# PHP.net
KiCad netlist of a schematic drawn in Altium Designer
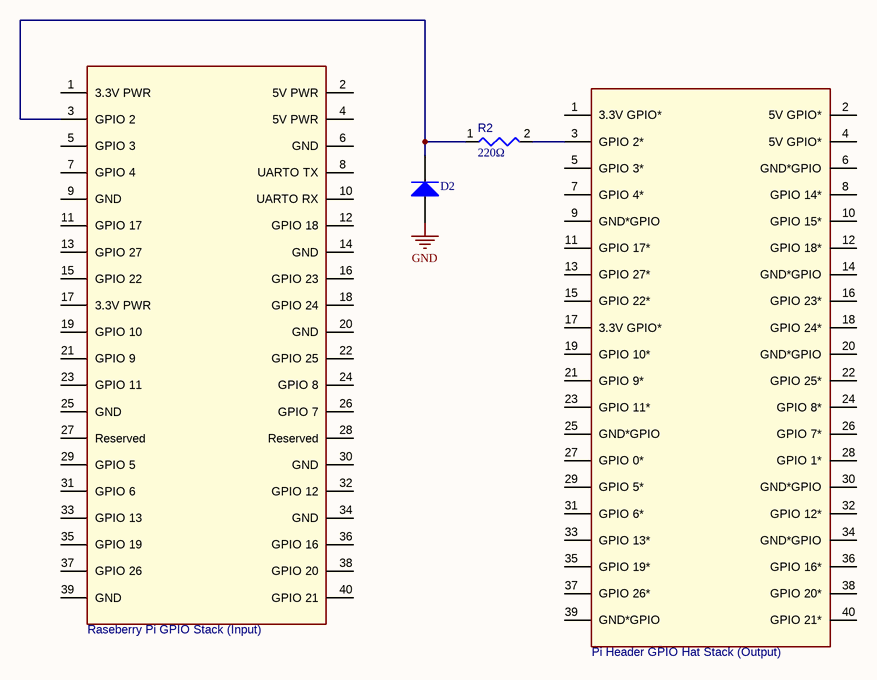
[diagram p0: PHP.SchDoc]

(export (version "E")
  (design (tool "Eeschema 10.0.6"))
  (components
    (comp (ref "D2")
      (value "1N4148")
      (footprint "NXP-SOD27-2_V")
      (description "High Speed Diode, 100 V, 0.45 A, -65 to 175 degC, 2-Pin SOD27, RoHS, Bulk")
      (fields (field (name "POWER") "500mW") (field (name "MANUFACTURER") "Fairchild"))
      (libsource (lib "Alexander Egan") (part "D-AK-2"))
    )
    (comp (ref "J1")
      (value "Raseberry Pi GPIO Stack (Input)")
      (footprint "TECO-1746540-4_V")
      (description "Connector")
      (libsource (lib "") (part "CMP-02187-7_1"))
    )
    (comp (ref "J2")
      (value "Pi Header GPIO Hat Stack (Output)")
      (footprint "TECO-1746540-4_V")
      (description "Connector")
      (libsource (lib "CMP-02187-7") (part "CMP-02187-7"))
    )
    (comp (ref "R2")
      (value "220Ω")
      (footprint "RESC1608X55X25ML10T15")
      (description "Chip Resistor, 4.7 KOhm, +/- 1%, 0.1 W, -55 to 155 degC, 0603 (1608 Metric)")
      (fields (field (name "TOLERANCE") "1%") (field (name "POWER") "100mW"))
      (libsource (lib "Alexander Egan") (part "RES-2"))
    )
  )
  (nets
    (net (code "1") (name "GND") (class "Default")
      (node (ref "D2") (pin "1") (pinfunction "A_1") (pintype "passive"))
    )
    (net (code "2") (name "Net-(D2-K)") (class "Default")
      (node (ref "D2") (pin "2") (pinfunction "K_2") (pintype "passive"))
      (node (ref "J1") (pin "3") (pinfunction "GPIO_2_3") (pintype "passive"))
      (node (ref "R2") (pin "1") (pinfunction "1_1") (pintype "passive"))
    )
    (net (code "3") (name "Net-(J2B-GPIO_2*)") (class "Default")
      (node (ref "J2") (pin "3") (pinfunction "GPIO_2*_3") (pintype "passive"))
      (node (ref "R2") (pin "2") (pinfunction "2_2") (pintype "passive"))
    )
    (net (code "4") (name "unconnected-(J1-3.3V_PWR-Pad1)") (class "Default")
      (node (ref "J1") (pin "1") (pinfunction "3.3V_PWR_1") (pintype "passive"))
    )
    (net (code "5") (name "unconnected-(J1-3.3V_PWR-Pad17)") (class "Default")
      (node (ref "J1") (pin "17") (pinfunction "3.3V_PWR_17") (pintype "passive"))
    )
    (net (code "6") (name "unconnected-(J1-5V_PWR-Pad2)") (class "Default")
      (node (ref "J1") (pin "2") (pinfunction "5V_PWR_2") (pintype "passive"))
    )
    (net (code "7") (name "unconnected-(J1-5V_PWR-Pad4)") (class "Default")
      (node (ref "J1") (pin "4") (pinfunction "5V_PWR_4") (pintype "passive"))
    )
    (net (code "8") (name "unconnected-(J1-GND-Pad6)") (class "Default")
      (node (ref "J1") (pin "6") (pinfunction "GND_6") (pintype "passive"))
    )
    (net (code "9") (name "unconnected-(J1-GND-Pad9)") (class "Default")
      (node (ref "J1") (pin "9") (pinfunction "GND_9") (pintype "passive"))
    )
    (net (code "10") (name "unconnected-(J1-GND-Pad14)") (class "Default")
      (node (ref "J1") (pin "14") (pinfunction "GND_14") (pintype "passive"))
    )
    (net (code "11") (name "unconnected-(J1-GND-Pad20)") (class "Default")
      (node (ref "J1") (pin "20") (pinfunction "GND_20") (pintype "passive"))
    )
    (net (code "12") (name "unconnected-(J1-GND-Pad25)") (class "Default")
      (node (ref "J1") (pin "25") (pinfunction "GND_25") (pintype "passive"))
    )
    (net (code "13") (name "unconnected-(J1-GND-Pad30)") (class "Default")
      (node (ref "J1") (pin "30") (pinfunction "GND_30") (pintype "passive"))
    )
    (net (code "14") (name "unconnected-(J1-GND-Pad34)") (class "Default")
      (node (ref "J1") (pin "34") (pinfunction "GND_34") (pintype "passive"))
    )
    (net (code "15") (name "unconnected-(J1-GND-Pad39)") (class "Default")
      (node (ref "J1") (pin "39") (pinfunction "GND_39") (pintype "passive"))
    )
    (net (code "16") (name "unconnected-(J1-GPIO_3-Pad5)") (class "Default")
      (node (ref "J1") (pin "5") (pinfunction "GPIO_3_5") (pintype "passive"))
    )
    (net (code "17") (name "unconnected-(J1-GPIO_4-Pad7)") (class "Default")
      (node (ref "J1") (pin "7") (pinfunction "GPIO_4_7") (pintype "passive"))
    )
    (net (code "18") (name "unconnected-(J1-GPIO_5-Pad29)") (class "Default")
      (node (ref "J1") (pin "29") (pinfunction "GPIO_5_29") (pintype "passive"))
    )
    (net (code "19") (name "unconnected-(J1-GPIO_6-Pad31)") (class "Default")
      (node (ref "J1") (pin "31") (pinfunction "GPIO_6_31") (pintype "passive"))
    )
    (net (code "20") (name "unconnected-(J1-GPIO_7-Pad26)") (class "Default")
      (node (ref "J1") (pin "26") (pinfunction "GPIO_7_26") (pintype "passive"))
    )
    (net (code "21") (name "unconnected-(J1-GPIO_8-Pad24)") (class "Default")
      (node (ref "J1") (pin "24") (pinfunction "GPIO_8_24") (pintype "passive"))
    )
    (net (code "22") (name "unconnected-(J1-GPIO_9-Pad21)") (class "Default")
      (node (ref "J1") (pin "21") (pinfunction "GPIO_9_21") (pintype "passive"))
    )
    (net (code "23") (name "unconnected-(J1-GPIO_10-Pad19)") (class "Default")
      (node (ref "J1") (pin "19") (pinfunction "GPIO_10_19") (pintype "passive"))
    )
    (net (code "24") (name "unconnected-(J1-GPIO_11-Pad23)") (class "Default")
      (node (ref "J1") (pin "23") (pinfunction "GPIO_11_23") (pintype "passive"))
    )
    (net (code "25") (name "unconnected-(J1-GPIO_12-Pad32)") (class "Default")
      (node (ref "J1") (pin "32") (pinfunction "GPIO_12_32") (pintype "passive"))
    )
    (net (code "26") (name "unconnected-(J1-GPIO_13-Pad33)") (class "Default")
      (node (ref "J1") (pin "33") (pinfunction "GPIO_13_33") (pintype "passive"))
    )
    (net (code "27") (name "unconnected-(J1-GPIO_16-Pad36)") (class "Default")
      (node (ref "J1") (pin "36") (pinfunction "GPIO_16_36") (pintype "passive"))
    )
    (net (code "28") (name "unconnected-(J1-GPIO_17-Pad11)") (class "Default")
      (node (ref "J1") (pin "11") (pinfunction "GPIO_17_11") (pintype "passive"))
    )
    (net (code "29") (name "unconnected-(J1-GPIO_18-Pad12)") (class "Default")
      (node (ref "J1") (pin "12") (pinfunction "GPIO_18_12") (pintype "passive"))
    )
    (net (code "30") (name "unconnected-(J1-GPIO_19-Pad35)") (class "Default")
      (node (ref "J1") (pin "35") (pinfunction "GPIO_19_35") (pintype "passive"))
    )
    (net (code "31") (name "unconnected-(J1-GPIO_20-Pad38)") (class "Default")
      (node (ref "J1") (pin "38") (pinfunction "GPIO_20_38") (pintype "passive"))
    )
    (net (code "32") (name "unconnected-(J1-GPIO_21-Pad40)") (class "Default")
      (node (ref "J1") (pin "40") (pinfunction "GPIO_21_40") (pintype "passive"))
    )
    (net (code "33") (name "unconnected-(J1-GPIO_22-Pad15)") (class "Default")
      (node (ref "J1") (pin "15") (pinfunction "GPIO_22_15") (pintype "passive"))
    )
    (net (code "34") (name "unconnected-(J1-GPIO_23-Pad16)") (class "Default")
      (node (ref "J1") (pin "16") (pinfunction "GPIO_23_16") (pintype "passive"))
    )
    (net (code "35") (name "unconnected-(J1-GPIO_24-Pad18)") (class "Default")
      (node (ref "J1") (pin "18") (pinfunction "GPIO_24_18") (pintype "passive"))
    )
    (net (code "36") (name "unconnected-(J1-GPIO_25-Pad22)") (class "Default")
      (node (ref "J1") (pin "22") (pinfunction "GPIO_25_22") (pintype "passive"))
    )
    (net (code "37") (name "unconnected-(J1-GPIO_26-Pad37)") (class "Default")
      (node (ref "J1") (pin "37") (pinfunction "GPIO_26_37") (pintype "passive"))
    )
    (net (code "38") (name "unconnected-(J1-GPIO_27-Pad13)") (class "Default")
      (node (ref "J1") (pin "13") (pinfunction "GPIO_27_13") (pintype "passive"))
    )
    (net (code "39") (name "unconnected-(J1-Reserved-Pad27)") (class "Default")
      (node (ref "J1") (pin "27") (pinfunction "Reserved_27") (pintype "passive"))
    )
    (net (code "40") (name "unconnected-(J1-Reserved-Pad28)") (class "Default")
      (node (ref "J1") (pin "28") (pinfunction "Reserved_28") (pintype "passive"))
    )
    (net (code "41") (name "unconnected-(J1-UARTO_RX-Pad10)") (class "Default")
      (node (ref "J1") (pin "10") (pinfunction "UARTO_RX_10") (pintype "passive"))
    )
    (net (code "42") (name "unconnected-(J1-UARTO_TX-Pad8)") (class "Default")
      (node (ref "J1") (pin "8") (pinfunction "UARTO_TX_8") (pintype "passive"))
    )
    (net (code "43") (name "unconnected-(J2B-3.3V_GPIO*-Pad1)") (class "Default")
      (node (ref "J2") (pin "1") (pinfunction "3.3V_GPIO*_1") (pintype "passive"))
    )
    (net (code "44") (name "unconnected-(J2B-3.3V_GPIO*-Pad17)") (class "Default")
      (node (ref "J2") (pin "17") (pinfunction "3.3V_GPIO*_17") (pintype "passive"))
    )
    (net (code "45") (name "unconnected-(J2B-5V_GPIO*-Pad2)") (class "Default")
      (node (ref "J2") (pin "2") (pinfunction "5V_GPIO*_2") (pintype "passive"))
    )
    (net (code "46") (name "unconnected-(J2B-5V_GPIO*-Pad4)") (class "Default")
      (node (ref "J2") (pin "4") (pinfunction "5V_GPIO*_4") (pintype "passive"))
    )
    (net (code "47") (name "unconnected-(J2B-GND*GPIO-Pad6)") (class "Default")
      (node (ref "J2") (pin "6") (pinfunction "GND*GPIO_6") (pintype "passive"))
    )
    (net (code "48") (name "unconnected-(J2B-GND*GPIO-Pad9)") (class "Default")
      (node (ref "J2") (pin "9") (pinfunction "GND*GPIO_9") (pintype "passive"))
    )
    (net (code "49") (name "unconnected-(J2B-GND*GPIO-Pad14)") (class "Default")
      (node (ref "J2") (pin "14") (pinfunction "GND*GPIO_14") (pintype "passive"))
    )
    (net (code "50") (name "unconnected-(J2B-GND*GPIO-Pad20)") (class "Default")
      (node (ref "J2") (pin "20") (pinfunction "GND*GPIO_20") (pintype "passive"))
    )
    (net (code "51") (name "unconnected-(J2B-GND*GPIO-Pad25)") (class "Default")
      (node (ref "J2") (pin "25") (pinfunction "GND*GPIO_25") (pintype "passive"))
    )
    (net (code "52") (name "unconnected-(J2B-GND*GPIO-Pad30)") (class "Default")
      (node (ref "J2") (pin "30") (pinfunction "GND*GPIO_30") (pintype "passive"))
    )
    (net (code "53") (name "unconnected-(J2B-GND*GPIO-Pad34)") (class "Default")
      (node (ref "J2") (pin "34") (pinfunction "GND*GPIO_34") (pintype "passive"))
    )
    (net (code "54") (name "unconnected-(J2B-GND*GPIO-Pad39)") (class "Default")
      (node (ref "J2") (pin "39") (pinfunction "GND*GPIO_39") (pintype "passive"))
    )
    (net (code "55") (name "unconnected-(J2B-GPIO_0*-Pad27)") (class "Default")
      (node (ref "J2") (pin "27") (pinfunction "GPIO_0*_27") (pintype "passive"))
    )
    (net (code "56") (name "unconnected-(J2B-GPIO_1*-Pad28)") (class "Default")
      (node (ref "J2") (pin "28") (pinfunction "GPIO_1*_28") (pintype "passive"))
    )
    (net (code "57") (name "unconnected-(J2B-GPIO_3*-Pad5)") (class "Default")
      (node (ref "J2") (pin "5") (pinfunction "GPIO_3*_5") (pintype "passive"))
    )
    (net (code "58") (name "unconnected-(J2B-GPIO_4*-Pad7)") (class "Default")
      (node (ref "J2") (pin "7") (pinfunction "GPIO_4*_7") (pintype "passive"))
    )
    (net (code "59") (name "unconnected-(J2B-GPIO_5*-Pad29)") (class "Default")
      (node (ref "J2") (pin "29") (pinfunction "GPIO_5*_29") (pintype "passive"))
    )
    (net (code "60") (name "unconnected-(J2B-GPIO_6*-Pad31)") (class "Default")
      (node (ref "J2") (pin "31") (pinfunction "GPIO_6*_31") (pintype "passive"))
    )
    (net (code "61") (name "unconnected-(J2B-GPIO_7*-Pad26)") (class "Default")
      (node (ref "J2") (pin "26") (pinfunction "GPIO_7*_26") (pintype "passive"))
    )
    (net (code "62") (name "unconnected-(J2B-GPIO_8*-Pad24)") (class "Default")
      (node (ref "J2") (pin "24") (pinfunction "GPIO_8*_24") (pintype "passive"))
    )
    (net (code "63") (name "unconnected-(J2B-GPIO_9*-Pad21)") (class "Default")
      (node (ref "J2") (pin "21") (pinfunction "GPIO_9*_21") (pintype "passive"))
    )
    (net (code "64") (name "unconnected-(J2B-GPIO_10*-Pad19)") (class "Default")
      (node (ref "J2") (pin "19") (pinfunction "GPIO_10*_19") (pintype "passive"))
    )
    (net (code "65") (name "unconnected-(J2B-GPIO_11*-Pad23)") (class "Default")
      (node (ref "J2") (pin "23") (pinfunction "GPIO_11*_23") (pintype "passive"))
    )
    (net (code "66") (name "unconnected-(J2B-GPIO_12*-Pad32)") (class "Default")
      (node (ref "J2") (pin "32") (pinfunction "GPIO_12*_32") (pintype "passive"))
    )
    (net (code "67") (name "unconnected-(J2B-GPIO_13*-Pad33)") (class "Default")
      (node (ref "J2") (pin "33") (pinfunction "GPIO_13*_33") (pintype "passive"))
    )
    (net (code "68") (name "unconnected-(J2B-GPIO_14*-Pad8)") (class "Default")
      (node (ref "J2") (pin "8") (pinfunction "GPIO_14*_8") (pintype "passive"))
    )
    (net (code "69") (name "unconnected-(J2B-GPIO_15*-Pad10)") (class "Default")
      (node (ref "J2") (pin "10") (pinfunction "GPIO_15*_10") (pintype "passive"))
    )
    (net (code "70") (name "unconnected-(J2B-GPIO_16*-Pad36)") (class "Default")
      (node (ref "J2") (pin "36") (pinfunction "GPIO_16*_36") (pintype "passive"))
    )
    (net (code "71") (name "unconnected-(J2B-GPIO_17*-Pad11)") (class "Default")
      (node (ref "J2") (pin "11") (pinfunction "GPIO_17*_11") (pintype "passive"))
    )
    (net (code "72") (name "unconnected-(J2B-GPIO_18*-Pad12)") (class "Default")
      (node (ref "J2") (pin "12") (pinfunction "GPIO_18*_12") (pintype "passive"))
    )
    (net (code "73") (name "unconnected-(J2B-GPIO_19*-Pad35)") (class "Default")
      (node (ref "J2") (pin "35") (pinfunction "GPIO_19*_35") (pintype "passive"))
    )
    (net (code "74") (name "unconnected-(J2B-GPIO_20*-Pad38)") (class "Default")
      (node (ref "J2") (pin "38") (pinfunction "GPIO_20*_38") (pintype "passive"))
    )
    (net (code "75") (name "unconnected-(J2B-GPIO_21*-Pad40)") (class "Default")
      (node (ref "J2") (pin "40") (pinfunction "GPIO_21*_40") (pintype "passive"))
    )
    (net (code "76") (name "unconnected-(J2B-GPIO_22*-Pad15)") (class "Default")
      (node (ref "J2") (pin "15") (pinfunction "GPIO_22*_15") (pintype "passive"))
    )
    (net (code "77") (name "unconnected-(J2B-GPIO_23*-Pad16)") (class "Default")
      (node (ref "J2") (pin "16") (pinfunction "GPIO_23*_16") (pintype "passive"))
    )
    (net (code "78") (name "unconnected-(J2B-GPIO_24*-Pad18)") (class "Default")
      (node (ref "J2") (pin "18") (pinfunction "GPIO_24*_18") (pintype "passive"))
    )
    (net (code "79") (name "unconnected-(J2B-GPIO_25*-Pad22)") (class "Default")
      (node (ref "J2") (pin "22") (pinfunction "GPIO_25*_22") (pintype "passive"))
    )
    (net (code "80") (name "unconnected-(J2B-GPIO_26*-Pad37)") (class "Default")
      (node (ref "J2") (pin "37") (pinfunction "GPIO_26*_37") (pintype "passive"))
    )
    (net (code "81") (name "unconnected-(J2B-GPIO_27*-Pad13)") (class "Default")
      (node (ref "J2") (pin "13") (pinfunction "GPIO_27*_13") (pintype "passive"))
    )
  )
)
